# POWER_SWITCH.net
KiCad netlist of a schematic drawn in Altium Designer
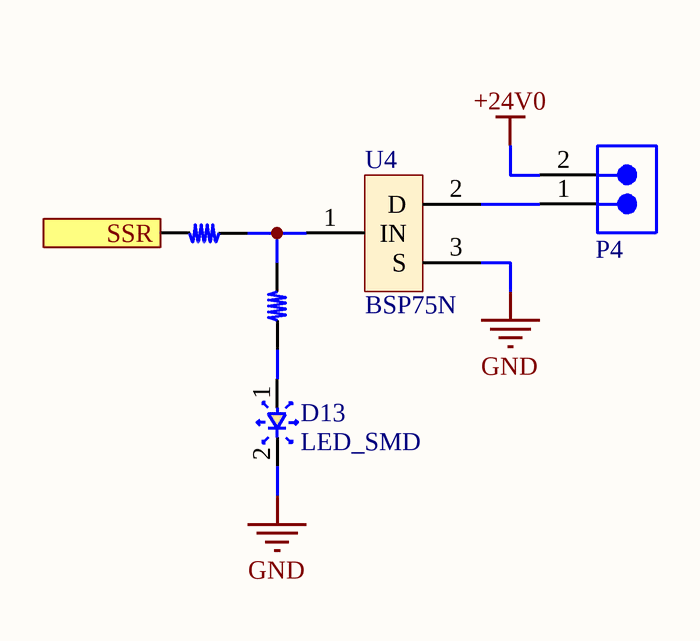
[diagram p0: POWER_SWITCH.SchDoc]

(export (version "E")
  (design (tool "Eeschema 10.0.6"))
  (components
    (comp (ref "D13")
      (value "LED_SMD")
      (footprint "D 0603")
      (libsource (lib "radmehr_library") (part "LED_SMD"))
    )
    (comp (ref "P4")
      (value "691321300002")
      (footprint "691321300002")
      (description "WR-TBL Series 321 Vertical PCB Header, Through Hole, pitch 3.81mm, 2p")
      (fields (field (name "MANUFACTURER") "Wurth Elektronik"))
      (libsource (lib "Altium_WR-TBL (rev22a)") (part "691321300002"))
    )
    (comp (ref "R12")
      (value "RES_SMD")
      (footprint "R 0603")
      (libsource (lib "radmehr_library") (part "RES_SMD"))
    )
    (comp (ref "R13")
      (value "RES_SMD")
      (footprint "R 0603")
      (libsource (lib "radmehr_library") (part "RES_SMD"))
    )
    (comp (ref "U4")
      (value "BSP75N")
      (footprint "SOT-223 - BSP75N")
      (libsource (lib "radmehr_library") (part "BSP75N"))
    )
  )
  (nets
    (net (code "1") (name "+24V0") (class "Default")
      (node (ref "P4") (pin "2") (pinfunction "2_2") (pintype "passive"))
    )
    (net (code "2") (name "/SSR") (class "Default")
      (node (ref "R12") (pin "2") (pinfunction "2_2") (pintype "passive"))
    )
    (net (code "3") (name "GND") (class "Default")
      (node (ref "D13") (pin "2") (pintype "passive"))
      (node (ref "U4") (pin "3") (pinfunction "S_3") (pintype "power_in"))
    )
    (net (code "4") (name "Net-(D13-Pad1)") (class "Default")
      (node (ref "D13") (pin "1") (pintype "passive"))
      (node (ref "R13") (pin "1") (pinfunction "1_1") (pintype "passive"))
    )
    (net (code "5") (name "Net-(U4-D)") (class "Default")
      (node (ref "P4") (pin "1") (pinfunction "1_1") (pintype "passive"))
      (node (ref "U4") (pin "2") (pinfunction "D_2") (pintype "power_in"))
    )
    (net (code "6") (name "Net-(U4-IN)") (class "Default")
      (node (ref "R12") (pin "1") (pinfunction "1_1") (pintype "passive"))
      (node (ref "R13") (pin "2") (pinfunction "2_2") (pintype "passive"))
      (node (ref "U4") (pin "1") (pinfunction "IN_1") (pintype "power_in"))
    )
  )
)
